# conduct-555-2.net
KiCad netlist of a schematic drawn in EAGLE
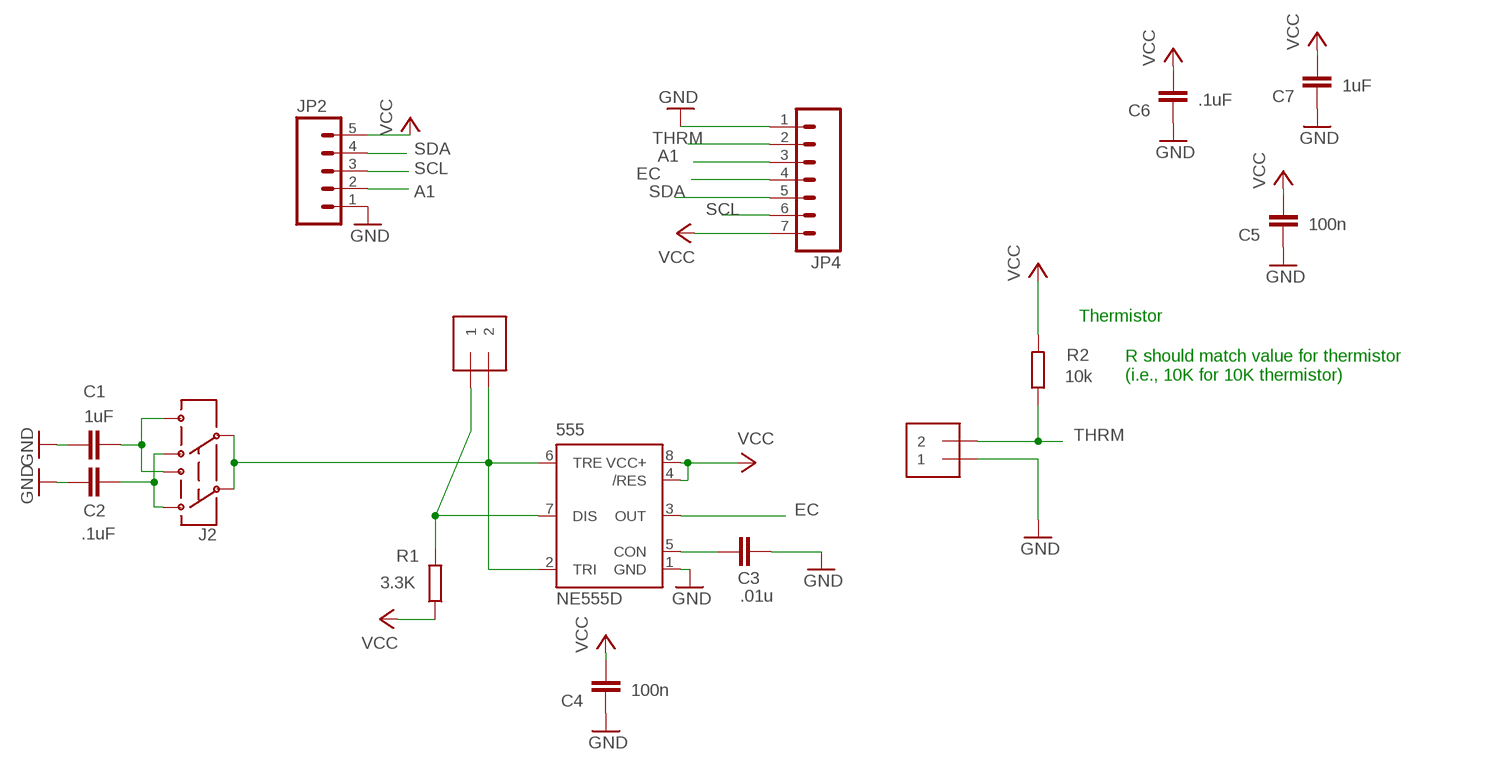
[diagram p0: schematic, sheet 1]

(export (version "E")
  (design (tool "Eeschema 10.0.6"))
  (components
    (comp (ref "555")
      (value "NE555D")
      (footprint "eagle-import:SO08@1")
      (libsource (lib "eagle-import") (part "NE555D"))
    )
    (comp (ref "C1")
      (value "1uF")
      (footprint "eagle-import:C0805")
      (libsource (lib "eagle-import") (part "C-EUC0805"))
    )
    (comp (ref "C2")
      (value ".1uF")
      (footprint "eagle-import:C0805")
      (libsource (lib "eagle-import") (part "C-EUC0805"))
    )
    (comp (ref "C3")
      (value ".01u")
      (footprint "eagle-import:C0805")
      (libsource (lib "eagle-import") (part "C-EUC0805"))
    )
    (comp (ref "C4")
      (value "100n")
      (footprint "eagle-import:C0805")
      (libsource (lib "eagle-import") (part "C-EUC0805"))
    )
    (comp (ref "C5")
      (value "100n")
      (footprint "eagle-import:C0805")
      (libsource (lib "eagle-import") (part "C-EUC0805"))
    )
    (comp (ref "C6")
      (value ".1uF")
      (footprint "eagle-import:C0805")
      (libsource (lib "eagle-import") (part "C-EUC0805"))
    )
    (comp (ref "C7")
      (value "1uF")
      (footprint "eagle-import:C0805")
      (libsource (lib "eagle-import") (part "C-EUC0805"))
    )
    (comp (ref "EC")
      (value "1X2-3.5MM")
      (footprint "eagle-import:1X2-3.5MM")
      (libsource (lib "eagle-import") (part "1X2-3.5MM"))
    )
    (comp (ref "J2")
      (value "AYZ0202")
      (footprint "eagle-import:AYZ0202")
      (libsource (lib "eagle-import") (part "AYZ0202"))
    )
    (comp (ref "JP2")
      (value "M05PTH")
      (footprint "eagle-import:1X05")
      (libsource (lib "eagle-import") (part "M05PTH"))
    )
    (comp (ref "JP4")
      (value "M07")
      (footprint "eagle-import:1X07")
      (libsource (lib "eagle-import") (part "M07"))
    )
    (comp (ref "R1")
      (value "3.3K")
      (footprint "eagle-import:R0805")
      (libsource (lib "eagle-import") (part "R-EU_R0805"))
    )
    (comp (ref "R2")
      (value "10k")
      (footprint "eagle-import:R0805")
      (libsource (lib "eagle-import") (part "R-EU_R0805"))
    )
    (comp (ref "THRM")
      (value "1X2-3.5MM")
      (footprint "eagle-import:1X2-3.5MM")
      (libsource (lib "eagle-import") (part "1X2-3.5MM"))
    )
  )
  (nets
    (net (code "1") (name "/A1") (class "Default")
      (node (ref "JP2") (pin "2") (pinfunction "2_2") (pintype "passive"))
      (node (ref "JP4") (pin "3") (pinfunction "3_3") (pintype "passive"))
    )
    (net (code "2") (name "/EC") (class "Default")
      (node (ref "555") (pin "3") (pinfunction "OUT_3") (pintype "output"))
      (node (ref "JP4") (pin "4") (pinfunction "4_4") (pintype "passive"))
    )
    (net (code "3") (name "/SCL") (class "Default")
      (node (ref "JP2") (pin "3") (pinfunction "3_3") (pintype "passive"))
      (node (ref "JP4") (pin "6") (pinfunction "6_6") (pintype "passive"))
    )
    (net (code "4") (name "/SDA") (class "Default")
      (node (ref "JP2") (pin "4") (pinfunction "4_4") (pintype "passive"))
      (node (ref "JP4") (pin "5") (pinfunction "5_5") (pintype "passive"))
    )
    (net (code "5") (name "/THRM") (class "Default")
      (node (ref "JP4") (pin "2") (pinfunction "2_2") (pintype "passive"))
      (node (ref "R2") (pin "1") (pinfunction "1_1") (pintype "passive"))
      (node (ref "THRM") (pin "2") (pinfunction "2_2") (pintype "passive"))
    )
    (net (code "6") (name "GND") (class "Default")
      (node (ref "555") (pin "1") (pinfunction "GND_1") (pintype "power_in"))
      (node (ref "C1") (pin "2") (pinfunction "2_2") (pintype "passive"))
      (node (ref "C2") (pin "2") (pinfunction "2_2") (pintype "passive"))
      (node (ref "C3") (pin "1") (pinfunction "1_1") (pintype "passive"))
      (node (ref "C4") (pin "1") (pinfunction "1_1") (pintype "passive"))
      (node (ref "C5") (pin "1") (pinfunction "1_1") (pintype "passive"))
      (node (ref "C6") (pin "1") (pinfunction "1_1") (pintype "passive"))
      (node (ref "C7") (pin "1") (pinfunction "1_1") (pintype "passive"))
      (node (ref "JP2") (pin "1") (pinfunction "1_1") (pintype "passive"))
      (node (ref "JP4") (pin "1") (pinfunction "1_1") (pintype "passive"))
      (node (ref "THRM") (pin "1") (pinfunction "1_1") (pintype "passive"))
    )
    (net (code "7") (name "Net-(555-CON)") (class "Default")
      (node (ref "555") (pin "5") (pinfunction "CON_5") (pintype "input"))
      (node (ref "C3") (pin "2") (pinfunction "2_2") (pintype "passive"))
    )
    (net (code "8") (name "Net-(555-DIS)") (class "Default")
      (node (ref "555") (pin "7") (pinfunction "DIS_7") (pintype "input"))
      (node (ref "EC") (pin "1") (pinfunction "1_1") (pintype "passive"))
      (node (ref "R1") (pin "2") (pinfunction "2_2") (pintype "passive"))
    )
    (net (code "9") (name "Net-(555-TRE)") (class "Default")
      (node (ref "555") (pin "2") (pinfunction "TRI_2") (pintype "input"))
      (node (ref "555") (pin "6") (pinfunction "TRE_6") (pintype "input"))
      (node (ref "EC") (pin "2") (pinfunction "2_2") (pintype "passive"))
      (node (ref "J2") (pin "2") (pinfunction "2_2") (pintype "bidirectional"))
      (node (ref "J2") (pin "5") (pinfunction "5_5") (pintype "bidirectional"))
    )
    (net (code "10") (name "Net-(J2-1)") (class "Default")
      (node (ref "C2") (pin "1") (pinfunction "1_1") (pintype "passive"))
      (node (ref "J2") (pin "3") (pinfunction "1_3") (pintype "bidirectional"))
      (node (ref "J2") (pin "6") (pinfunction "4_6") (pintype "bidirectional"))
    )
    (net (code "11") (name "Net-(J2-3)") (class "Default")
      (node (ref "C1") (pin "1") (pinfunction "1_1") (pintype "passive"))
      (node (ref "J2") (pin "1") (pinfunction "3_1") (pintype "bidirectional"))
      (node (ref "J2") (pin "4") (pinfunction "6_4") (pintype "bidirectional"))
    )
    (net (code "12") (name "VCC") (class "Default")
      (node (ref "555") (pin "4") (pinfunction "/RES_4") (pintype "input"))
      (node (ref "555") (pin "8") (pinfunction "VCC+_8") (pintype "power_in"))
      (node (ref "C4") (pin "2") (pinfunction "2_2") (pintype "passive"))
      (node (ref "C5") (pin "2") (pinfunction "2_2") (pintype "passive"))
      (node (ref "C6") (pin "2") (pinfunction "2_2") (pintype "passive"))
      (node (ref "C7") (pin "2") (pinfunction "2_2") (pintype "passive"))
      (node (ref "JP2") (pin "5") (pinfunction "5_5") (pintype "passive"))
      (node (ref "JP4") (pin "7") (pinfunction "7_7") (pintype "passive"))
      (node (ref "R1") (pin "1") (pinfunction "1_1") (pintype "passive"))
      (node (ref "R2") (pin "2") (pinfunction "2_2") (pintype "passive"))
    )
  )
)
